# Breakout.net
KiCad netlist of a schematic drawn in EAGLE
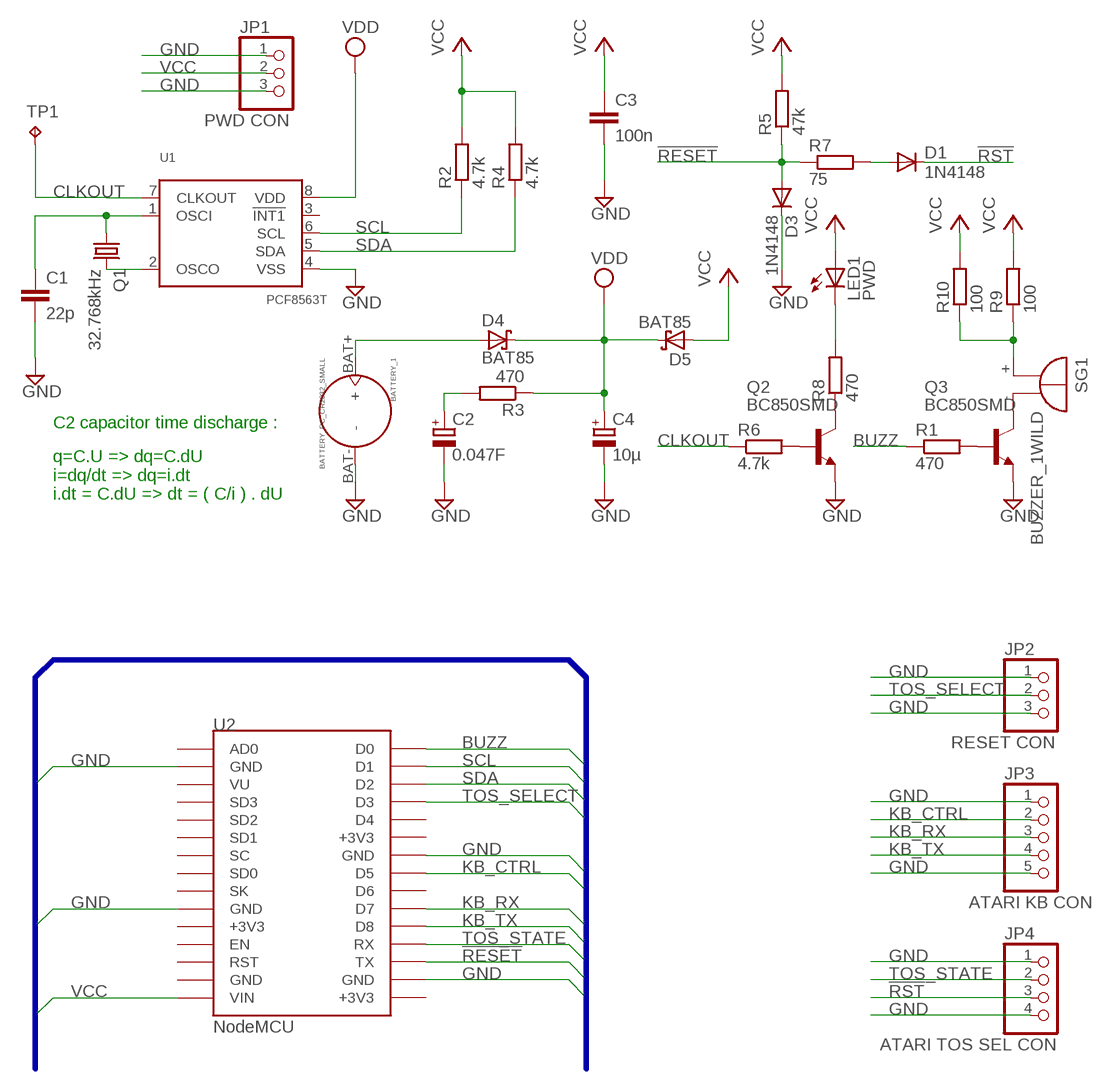
[diagram p0: schematic, sheet 1]

(export (version "E")
  (design (tool "Eeschema 10.0.6"))
  (components
    (comp (ref "BATTERY_1")
      (value "BATTERY_PC_CR2032_SMALL")
      (footprint "eagle-import:BATTERY_1236_SMALL")
      (libsource (lib "eagle-import") (part "BATTERY_PC_CR2032_SMALL"))
    )
    (comp (ref "C1")
      (value "22p")
      (footprint "eagle-import:C025-024X044")
      (libsource (lib "eagle-import") (part "C-EU025-024X044"))
    )
    (comp (ref "C2")
      (value "0.047F")
      (footprint "eagle-import:SCAP1")
      (libsource (lib "eagle-import") (part "SUPERCAP"))
    )
    (comp (ref "C3")
      (value "100n")
      (footprint "eagle-import:C050-025X075")
      (libsource (lib "eagle-import") (part "C-EU050-025X075"))
    )
    (comp (ref "C4")
      (value "10µ")
      (footprint "eagle-import:E2-5")
      (libsource (lib "eagle-import") (part "CPOL-EUE2-5"))
    )
    (comp (ref "D1")
      (value "1N4148")
      (footprint "eagle-import:DO35-5")
      (libsource (lib "eagle-import") (part "1N4148DO35-5"))
    )
    (comp (ref "D3")
      (value "1N4148")
      (footprint "eagle-import:DO35-7")
      (libsource (lib "eagle-import") (part "1N4148DO35-7"))
    )
    (comp (ref "D4")
      (value "BAT85")
      (footprint "eagle-import:DO41-10")
      (libsource (lib "eagle-import") (part "BAT85"))
    )
    (comp (ref "D5")
      (value "BAT85")
      (footprint "eagle-import:DO41-10")
      (libsource (lib "eagle-import") (part "BAT85"))
    )
    (comp (ref "JP1")
      (value "PWD CON")
      (footprint "eagle-import:1X03")
      (libsource (lib "eagle-import") (part "PINHD-1X3"))
    )
    (comp (ref "JP2")
      (value "RESET CON")
      (footprint "eagle-import:1X03")
      (libsource (lib "eagle-import") (part "PINHD-1X3"))
    )
    (comp (ref "JP3")
      (value "ATARI KB CON")
      (footprint "eagle-import:1X05")
      (libsource (lib "eagle-import") (part "PINHD-1X5"))
    )
    (comp (ref "JP4")
      (value "ATARI TOS SEL CON")
      (footprint "eagle-import:1X04")
      (libsource (lib "eagle-import") (part "PINHD-1X4"))
    )
    (comp (ref "LED1")
      (value "PWD")
      (footprint "eagle-import:LED5MM")
      (libsource (lib "eagle-import") (part "LED5MM"))
    )
    (comp (ref "Q1")
      (value "32.768kHz")
      (footprint "eagle-import:TC38H")
      (libsource (lib "eagle-import") (part "CRYSTALTC38H"))
    )
    (comp (ref "Q2")
      (value "BC850SMD")
      (footprint "eagle-import:SOT23-BEC")
      (libsource (lib "eagle-import") (part "BC850SMD"))
    )
    (comp (ref "Q3")
      (value "BC850SMD")
      (footprint "eagle-import:SOT23-BEC")
      (libsource (lib "eagle-import") (part "BC850SMD"))
    )
    (comp (ref "R1")
      (value "470")
      (footprint "eagle-import:M2012")
      (libsource (lib "eagle-import") (part "R-EU_M2012"))
    )
    (comp (ref "R2")
      (value "4.7k")
      (footprint "eagle-import:0204_7")
      (libsource (lib "eagle-import") (part "R-EU_0204/7"))
    )
    (comp (ref "R3")
      (value "470")
      (footprint "eagle-import:0204_7")
      (libsource (lib "eagle-import") (part "R-EU_0204/7"))
    )
    (comp (ref "R4")
      (value "4.7k")
      (footprint "eagle-import:0204_7")
      (libsource (lib "eagle-import") (part "R-EU_0204/7"))
    )
    (comp (ref "R5")
      (value "47k")
      (footprint "eagle-import:0204_7")
      (libsource (lib "eagle-import") (part "R-EU_0204/7"))
    )
    (comp (ref "R6")
      (value "4.7k")
      (footprint "eagle-import:0204_7")
      (libsource (lib "eagle-import") (part "R-EU_0204/7"))
    )
    (comp (ref "R7")
      (value "75")
      (footprint "eagle-import:0204_7")
      (libsource (lib "eagle-import") (part "R-EU_0204/7"))
    )
    (comp (ref "R8")
      (value "470")
      (footprint "eagle-import:M2012")
      (libsource (lib "eagle-import") (part "R-EU_M2012"))
    )
    (comp (ref "R9")
      (value "100")
      (footprint "eagle-import:M2012")
      (libsource (lib "eagle-import") (part "R-EU_M2012"))
    )
    (comp (ref "R10")
      (value "100")
      (footprint "eagle-import:0207_7")
      (libsource (lib "eagle-import") (part "R-EU_0207/7"))
    )
    (comp (ref "SG1")
      (value "BUZZER_1WILD")
      (footprint "eagle-import:F_QMBIII-W")
      (libsource (lib "eagle-import") (part "BUZZER_1WILD"))
    )
    (comp (ref "TP1")
      (value "TPTP19SQ")
      (footprint "eagle-import:TP19SQ")
      (libsource (lib "eagle-import") (part "TPTP19SQ"))
    )
    (comp (ref "U1")
      (value "PCF8563T")
      (footprint "eagle-import:SOT96-1")
      (libsource (lib "eagle-import") (part "PCF8563T"))
    )
    (comp (ref "U2")
      (value "NodeMCU")
      (footprint "eagle-import:NODE_MCU_V3_WILD_DIL")
      (libsource (lib "eagle-import") (part "NODE_MCU_V3DIL_WILD"))
    )
  )
  (nets
    (net (code "1") (name "/BUZZ") (class "Default")
      (node (ref "R1") (pin "1") (pinfunction "1_1") (pintype "passive"))
      (node (ref "U2") (pin "D0") (pinfunction "D0_D0") (pintype "bidirectional"))
    )
    (net (code "2") (name "/CLKOUT") (class "Default")
      (node (ref "R6") (pin "1") (pinfunction "1_1") (pintype "passive"))
      (node (ref "TP1") (pin "TP") (pinfunction "TP_TP") (pintype "input"))
      (node (ref "U1") (pin "7") (pinfunction "CLKOUT_7") (pintype "power_in"))
    )
    (net (code "3") (name "/KB_CTRL") (class "Default")
      (node (ref "JP3") (pin "2") (pinfunction "2_2") (pintype "passive"))
      (node (ref "U2") (pin "D5") (pinfunction "D5_D5") (pintype "bidirectional"))
    )
    (net (code "4") (name "/KB_RX") (class "Default")
      (node (ref "JP3") (pin "3") (pinfunction "3_3") (pintype "passive"))
      (node (ref "U2") (pin "D7") (pinfunction "D7_D7") (pintype "bidirectional"))
    )
    (net (code "5") (name "/KB_TX") (class "Default")
      (node (ref "JP3") (pin "4") (pinfunction "4_4") (pintype "passive"))
      (node (ref "U2") (pin "D8") (pinfunction "D8_D8") (pintype "bidirectional"))
    )
    (net (code "6") (name "/SCL") (class "Default")
      (node (ref "R2") (pin "1") (pinfunction "1_1") (pintype "passive"))
      (node (ref "U1") (pin "6") (pinfunction "SCL_6") (pintype "input"))
      (node (ref "U2") (pin "D1") (pinfunction "D1_D1") (pintype "bidirectional"))
    )
    (net (code "7") (name "/SDA") (class "Default")
      (node (ref "R4") (pin "1") (pinfunction "1_1") (pintype "passive"))
      (node (ref "U1") (pin "5") (pinfunction "SDA_5") (pintype "bidirectional"))
      (node (ref "U2") (pin "D2") (pinfunction "D2_D2") (pintype "bidirectional"))
    )
    (net (code "8") (name "/TOS_SELECT") (class "Default")
      (node (ref "JP2") (pin "2") (pinfunction "2_2") (pintype "passive"))
      (node (ref "U2") (pin "D3") (pinfunction "D3_D3") (pintype "bidirectional"))
    )
    (net (code "9") (name "/TOS_STATE") (class "Default")
      (node (ref "JP4") (pin "2") (pinfunction "2_2") (pintype "passive"))
      (node (ref "U2") (pin "RX") (pinfunction "RX_RX") (pintype "bidirectional"))
    )
    (net (code "10") (name "/~{RESET}") (class "Default")
      (node (ref "D3") (pin "A") (pinfunction "A_A") (pintype "passive"))
      (node (ref "R5") (pin "1") (pinfunction "1_1") (pintype "passive"))
      (node (ref "R7") (pin "1") (pinfunction "1_1") (pintype "passive"))
      (node (ref "U2") (pin "TX") (pinfunction "TX_TX") (pintype "bidirectional"))
    )
    (net (code "11") (name "/~{RST}") (class "Default")
      (node (ref "D1") (pin "C") (pinfunction "C_C") (pintype "passive"))
      (node (ref "JP4") (pin "3") (pinfunction "3_3") (pintype "passive"))
    )
    (net (code "12") (name "GND") (class "Default")
      (node (ref "BATTERY_1") (pin "BAT-") (pinfunction "-_BAT-") (pintype "bidirectional"))
      (node (ref "C1") (pin "2") (pinfunction "2_2") (pintype "passive"))
      (node (ref "C2") (pin "-") (pinfunction "-_-") (pintype "passive"))
      (node (ref "C3") (pin "2") (pinfunction "2_2") (pintype "passive"))
      (node (ref "C4") (pin "-") (pinfunction "-_-") (pintype "passive"))
      (node (ref "D3") (pin "C") (pinfunction "C_C") (pintype "passive"))
      (node (ref "JP1") (pin "1") (pinfunction "1_1") (pintype "passive"))
      (node (ref "JP1") (pin "3") (pinfunction "3_3") (pintype "passive"))
      (node (ref "JP2") (pin "1") (pinfunction "1_1") (pintype "passive"))
      (node (ref "JP2") (pin "3") (pinfunction "3_3") (pintype "passive"))
      (node (ref "JP3") (pin "1") (pinfunction "1_1") (pintype "passive"))
      (node (ref "JP3") (pin "5") (pinfunction "5_5") (pintype "passive"))
      (node (ref "JP4") (pin "1") (pinfunction "1_1") (pintype "passive"))
      (node (ref "JP4") (pin "4") (pinfunction "4_4") (pintype "passive"))
      (node (ref "Q2") (pin "E") (pinfunction "E_E") (pintype "passive"))
      (node (ref "Q3") (pin "E") (pinfunction "E_E") (pintype "passive"))
      (node (ref "U1") (pin "4") (pinfunction "VSS_4") (pintype "power_in"))
      (node (ref "U2") (pin "GND") (pinfunction "GND_GND") (pintype "power_in"))
      (node (ref "U2") (pin "GND@0") (pinfunction "GND_GND@0") (pintype "bidirectional"))
      (node (ref "U2") (pin "GND@2") (pinfunction "GND_GND@2") (pintype "bidirectional"))
      (node (ref "U2") (pin "GND@3") (pinfunction "GND_GND@3") (pintype "bidirectional"))
    )
    (net (code "13") (name "Net-(BATTERY_1-+)") (class "Default")
      (node (ref "BATTERY_1") (pin "BAT+") (pinfunction "+_BAT+") (pintype "bidirectional"))
      (node (ref "D4") (pin "A") (pinfunction "A_A") (pintype "passive"))
    )
    (net (code "14") (name "Net-(C2-Pad+)") (class "Default")
      (node (ref "C2") (pin "+") (pinfunction "+_+") (pintype "passive"))
      (node (ref "R3") (pin "2") (pinfunction "2_2") (pintype "passive"))
    )
    (net (code "15") (name "Net-(D1-PadA)") (class "Default")
      (node (ref "D1") (pin "A") (pinfunction "A_A") (pintype "passive"))
      (node (ref "R7") (pin "2") (pinfunction "2_2") (pintype "passive"))
    )
    (net (code "16") (name "Net-(LED1-C)") (class "Default")
      (node (ref "LED1") (pin "K") (pinfunction "C_K") (pintype "passive"))
      (node (ref "R8") (pin "2") (pinfunction "2_2") (pintype "passive"))
    )
    (net (code "17") (name "Net-(Q2-PadB)") (class "Default")
      (node (ref "Q2") (pin "B") (pinfunction "B_B") (pintype "passive"))
      (node (ref "R6") (pin "2") (pinfunction "2_2") (pintype "passive"))
    )
    (net (code "18") (name "Net-(Q2-PadC)") (class "Default")
      (node (ref "Q2") (pin "C") (pinfunction "C_C") (pintype "passive"))
      (node (ref "R8") (pin "1") (pinfunction "1_1") (pintype "passive"))
    )
    (net (code "19") (name "Net-(Q3-PadB)") (class "Default")
      (node (ref "Q3") (pin "B") (pinfunction "B_B") (pintype "passive"))
      (node (ref "R1") (pin "2") (pinfunction "2_2") (pintype "passive"))
    )
    (net (code "20") (name "Net-(Q3-PadC)") (class "Default")
      (node (ref "Q3") (pin "C") (pinfunction "C_C") (pintype "passive"))
      (node (ref "SG1") (pin "-") (pinfunction "-_-") (pintype "passive"))
    )
    (net (code "21") (name "Net-(R10-Pad1)") (class "Default")
      (node (ref "R10") (pin "1") (pinfunction "1_1") (pintype "passive"))
      (node (ref "R9") (pin "1") (pinfunction "1_1") (pintype "passive"))
      (node (ref "SG1") (pin "+") (pinfunction "+_+") (pintype "passive"))
    )
    (net (code "22") (name "Net-(U1-OSCI)") (class "Default")
      (node (ref "C1") (pin "1") (pinfunction "1_1") (pintype "passive"))
      (node (ref "Q1") (pin "1") (pinfunction "1_1") (pintype "passive"))
      (node (ref "U1") (pin "1") (pinfunction "OSCI_1") (pintype "passive"))
    )
    (net (code "23") (name "Net-(U1-OSCO)") (class "Default")
      (node (ref "Q1") (pin "2") (pinfunction "2_2") (pintype "passive"))
      (node (ref "U1") (pin "2") (pinfunction "OSCO_2") (pintype "passive"))
    )
    (net (code "24") (name "VCC") (class "Default")
      (node (ref "C3") (pin "1") (pinfunction "1_1") (pintype "passive"))
      (node (ref "D5") (pin "A") (pinfunction "A_A") (pintype "passive"))
      (node (ref "JP1") (pin "2") (pinfunction "2_2") (pintype "passive"))
      (node (ref "LED1") (pin "A") (pinfunction "A_A") (pintype "passive"))
      (node (ref "R10") (pin "2") (pinfunction "2_2") (pintype "passive"))
      (node (ref "R2") (pin "2") (pinfunction "2_2") (pintype "passive"))
      (node (ref "R4") (pin "2") (pinfunction "2_2") (pintype "passive"))
      (node (ref "R5") (pin "2") (pinfunction "2_2") (pintype "passive"))
      (node (ref "R9") (pin "2") (pinfunction "2_2") (pintype "passive"))
      (node (ref "U2") (pin "VIN") (pinfunction "VIN_VIN") (pintype "bidirectional"))
    )
    (net (code "25") (name "VDD") (class "Default")
      (node (ref "C4") (pin "+") (pinfunction "+_+") (pintype "passive"))
      (node (ref "D4") (pin "C") (pinfunction "C_C") (pintype "passive"))
      (node (ref "D5") (pin "C") (pinfunction "C_C") (pintype "passive"))
      (node (ref "R3") (pin "1") (pinfunction "1_1") (pintype "passive"))
      (node (ref "U1") (pin "8") (pinfunction "VDD_8") (pintype "power_in"))
    )
    (net (code "26") (name "unconnected-(U1-~{INT1}-Pad3)") (class "Default")
      (node (ref "U1") (pin "3") (pinfunction "~{INT1}_3") (pintype "output"))
    )
    (net (code "27") (name "unconnected-(U2-+3V3-Pad3V3@0)") (class "Default")
      (node (ref "U2") (pin "3V3@0") (pinfunction "+3V3_3V3@0") (pintype "bidirectional"))
    )
    (net (code "28") (name "unconnected-(U2-+3V3-Pad3V3@1)") (class "Default")
      (node (ref "U2") (pin "3V3@1") (pinfunction "+3V3_3V3@1") (pintype "bidirectional"))
    )
    (net (code "29") (name "unconnected-(U2-+3V3-Pad3V3@2)") (class "Default")
      (node (ref "U2") (pin "3V3@2") (pinfunction "+3V3_3V3@2") (pintype "bidirectional"))
    )
    (net (code "30") (name "unconnected-(U2-GND-PadGND@1)") (class "Default")
      (node (ref "U2") (pin "GND@1") (pinfunction "GND_GND@1") (pintype "bidirectional"))
    )
    (net (code "31") (name "unconnected-(U2-PadAD0)") (class "Default")
      (node (ref "U2") (pin "AD0") (pinfunction "AD0_AD0") (pintype "bidirectional"))
    )
    (net (code "32") (name "unconnected-(U2-PadD4)") (class "Default")
      (node (ref "U2") (pin "D4") (pinfunction "D4_D4") (pintype "bidirectional"))
    )
    (net (code "33") (name "unconnected-(U2-PadD6)") (class "Default")
      (node (ref "U2") (pin "D6") (pinfunction "D6_D6") (pintype "bidirectional"))
    )
    (net (code "34") (name "unconnected-(U2-PadEN)") (class "Default")
      (node (ref "U2") (pin "EN") (pinfunction "EN_EN") (pintype "bidirectional"))
    )
    (net (code "35") (name "unconnected-(U2-PadRST)") (class "Default")
      (node (ref "U2") (pin "RST") (pinfunction "RST_RST") (pintype "bidirectional"))
    )
    (net (code "36") (name "unconnected-(U2-PadSC)") (class "Default")
      (node (ref "U2") (pin "SC") (pinfunction "SC_SC") (pintype "bidirectional"))
    )
    (net (code "37") (name "unconnected-(U2-PadSD0)") (class "Default")
      (node (ref "U2") (pin "SD0") (pinfunction "SD0_SD0") (pintype "bidirectional"))
    )
    (net (code "38") (name "unconnected-(U2-PadSD1)") (class "Default")
      (node (ref "U2") (pin "SD1") (pinfunction "SD1_SD1") (pintype "bidirectional"))
    )
    (net (code "39") (name "unconnected-(U2-PadSD2)") (class "Default")
      (node (ref "U2") (pin "SD2") (pinfunction "SD2_SD2") (pintype "bidirectional"))
    )
    (net (code "40") (name "unconnected-(U2-PadSD3)") (class "Default")
      (node (ref "U2") (pin "SD3") (pinfunction "SD3_SD3") (pintype "bidirectional"))
    )
    (net (code "41") (name "unconnected-(U2-PadSK)") (class "Default")
      (node (ref "U2") (pin "SK") (pinfunction "SK_SK") (pintype "bidirectional"))
    )
    (net (code "42") (name "unconnected-(U2-PadVU)") (class "Default")
      (node (ref "U2") (pin "VU") (pinfunction "VU_VU") (pintype "passive"))
    )
  )
)
